# RetroBit.net
KiCad netlist of a schematic drawn in EAGLE
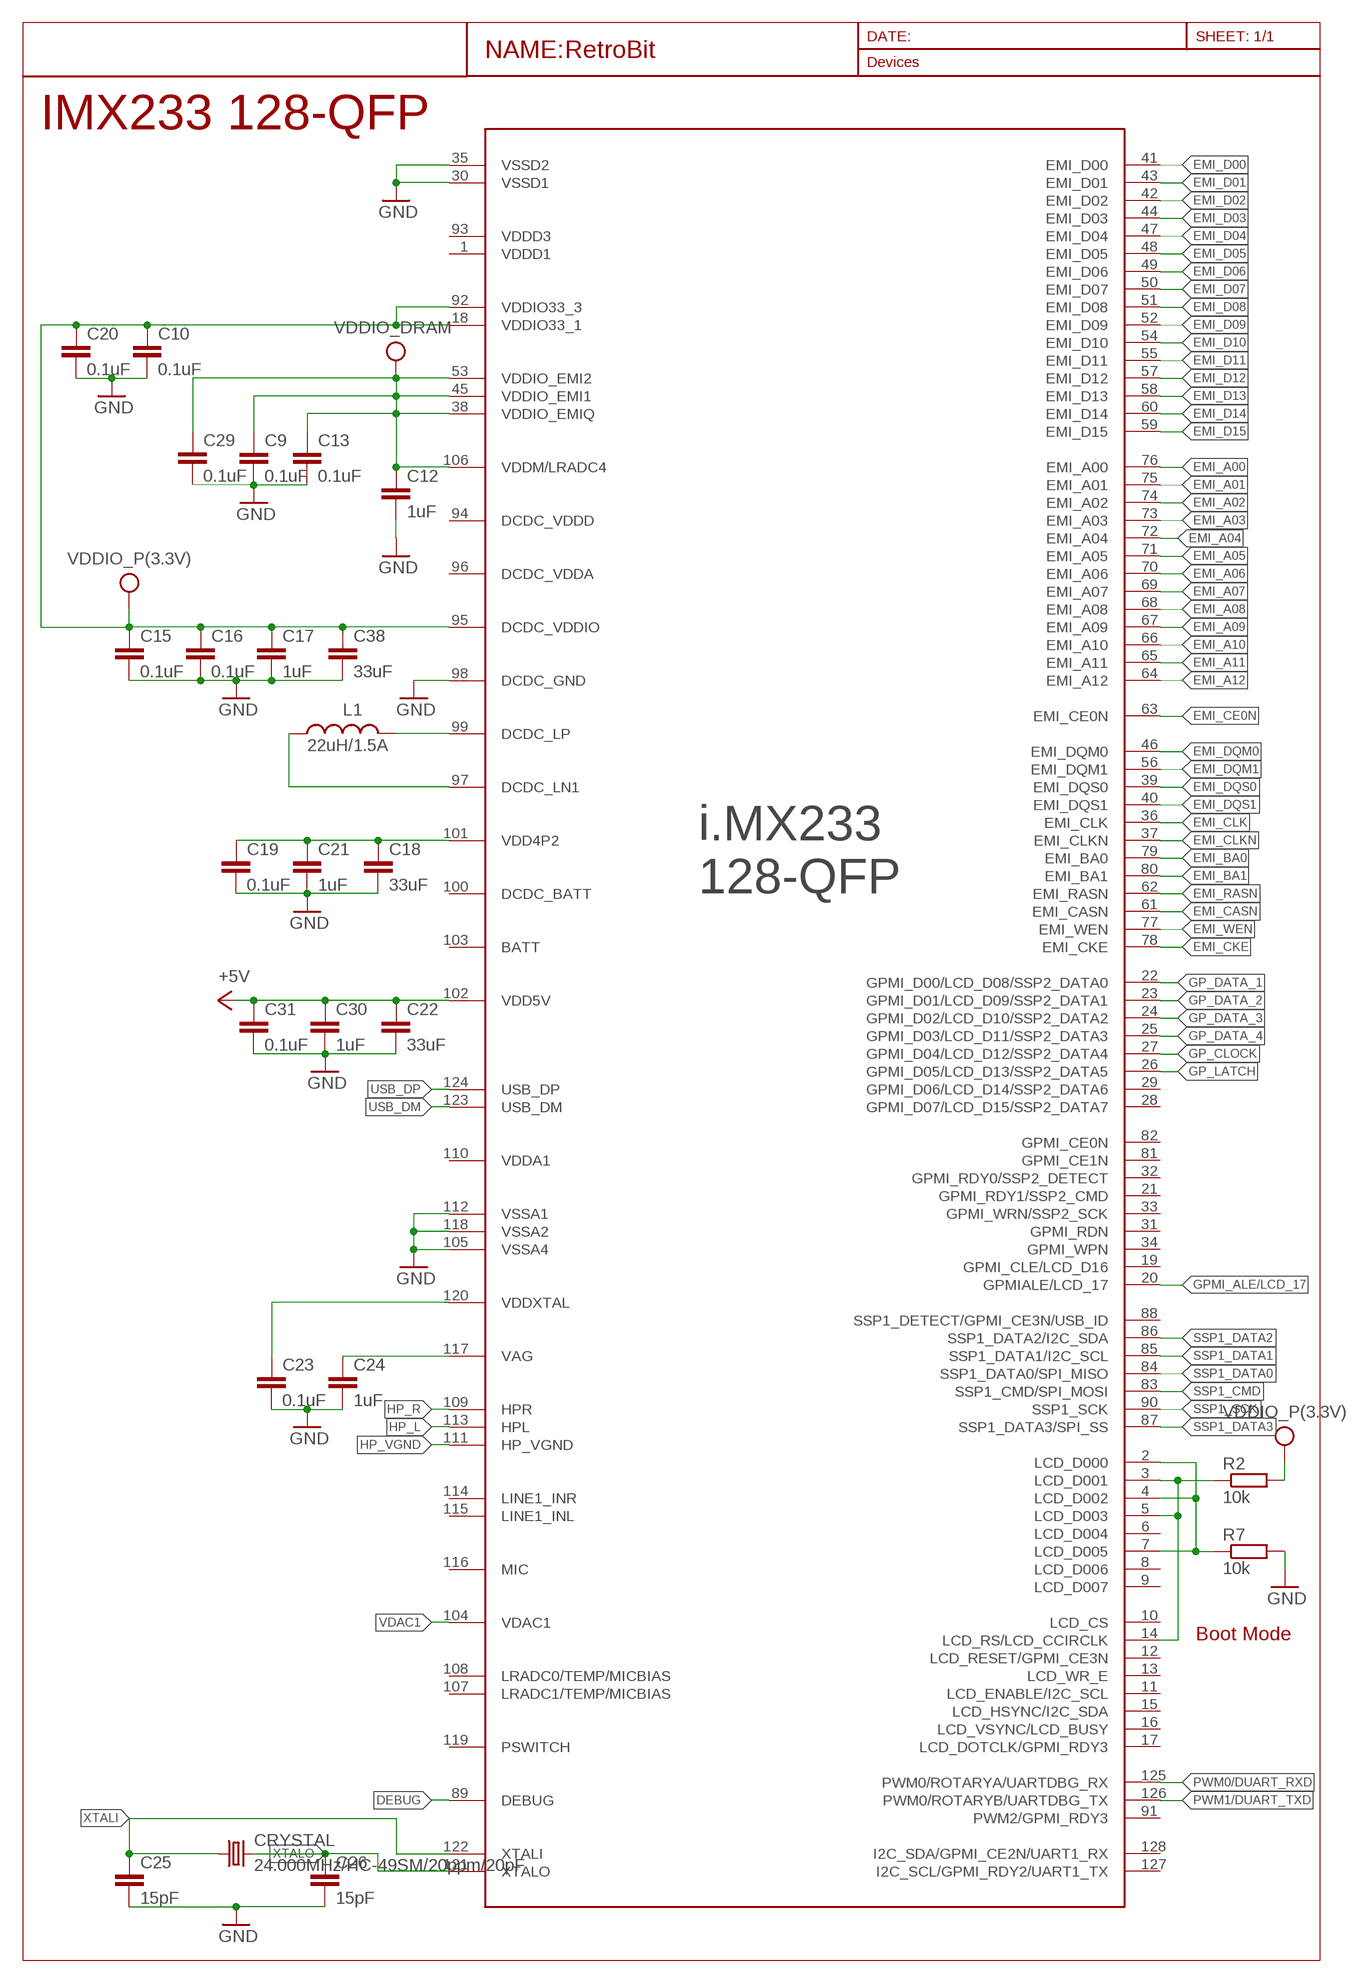
[diagram p0: schematic, sheet 1, part 1 of 2]
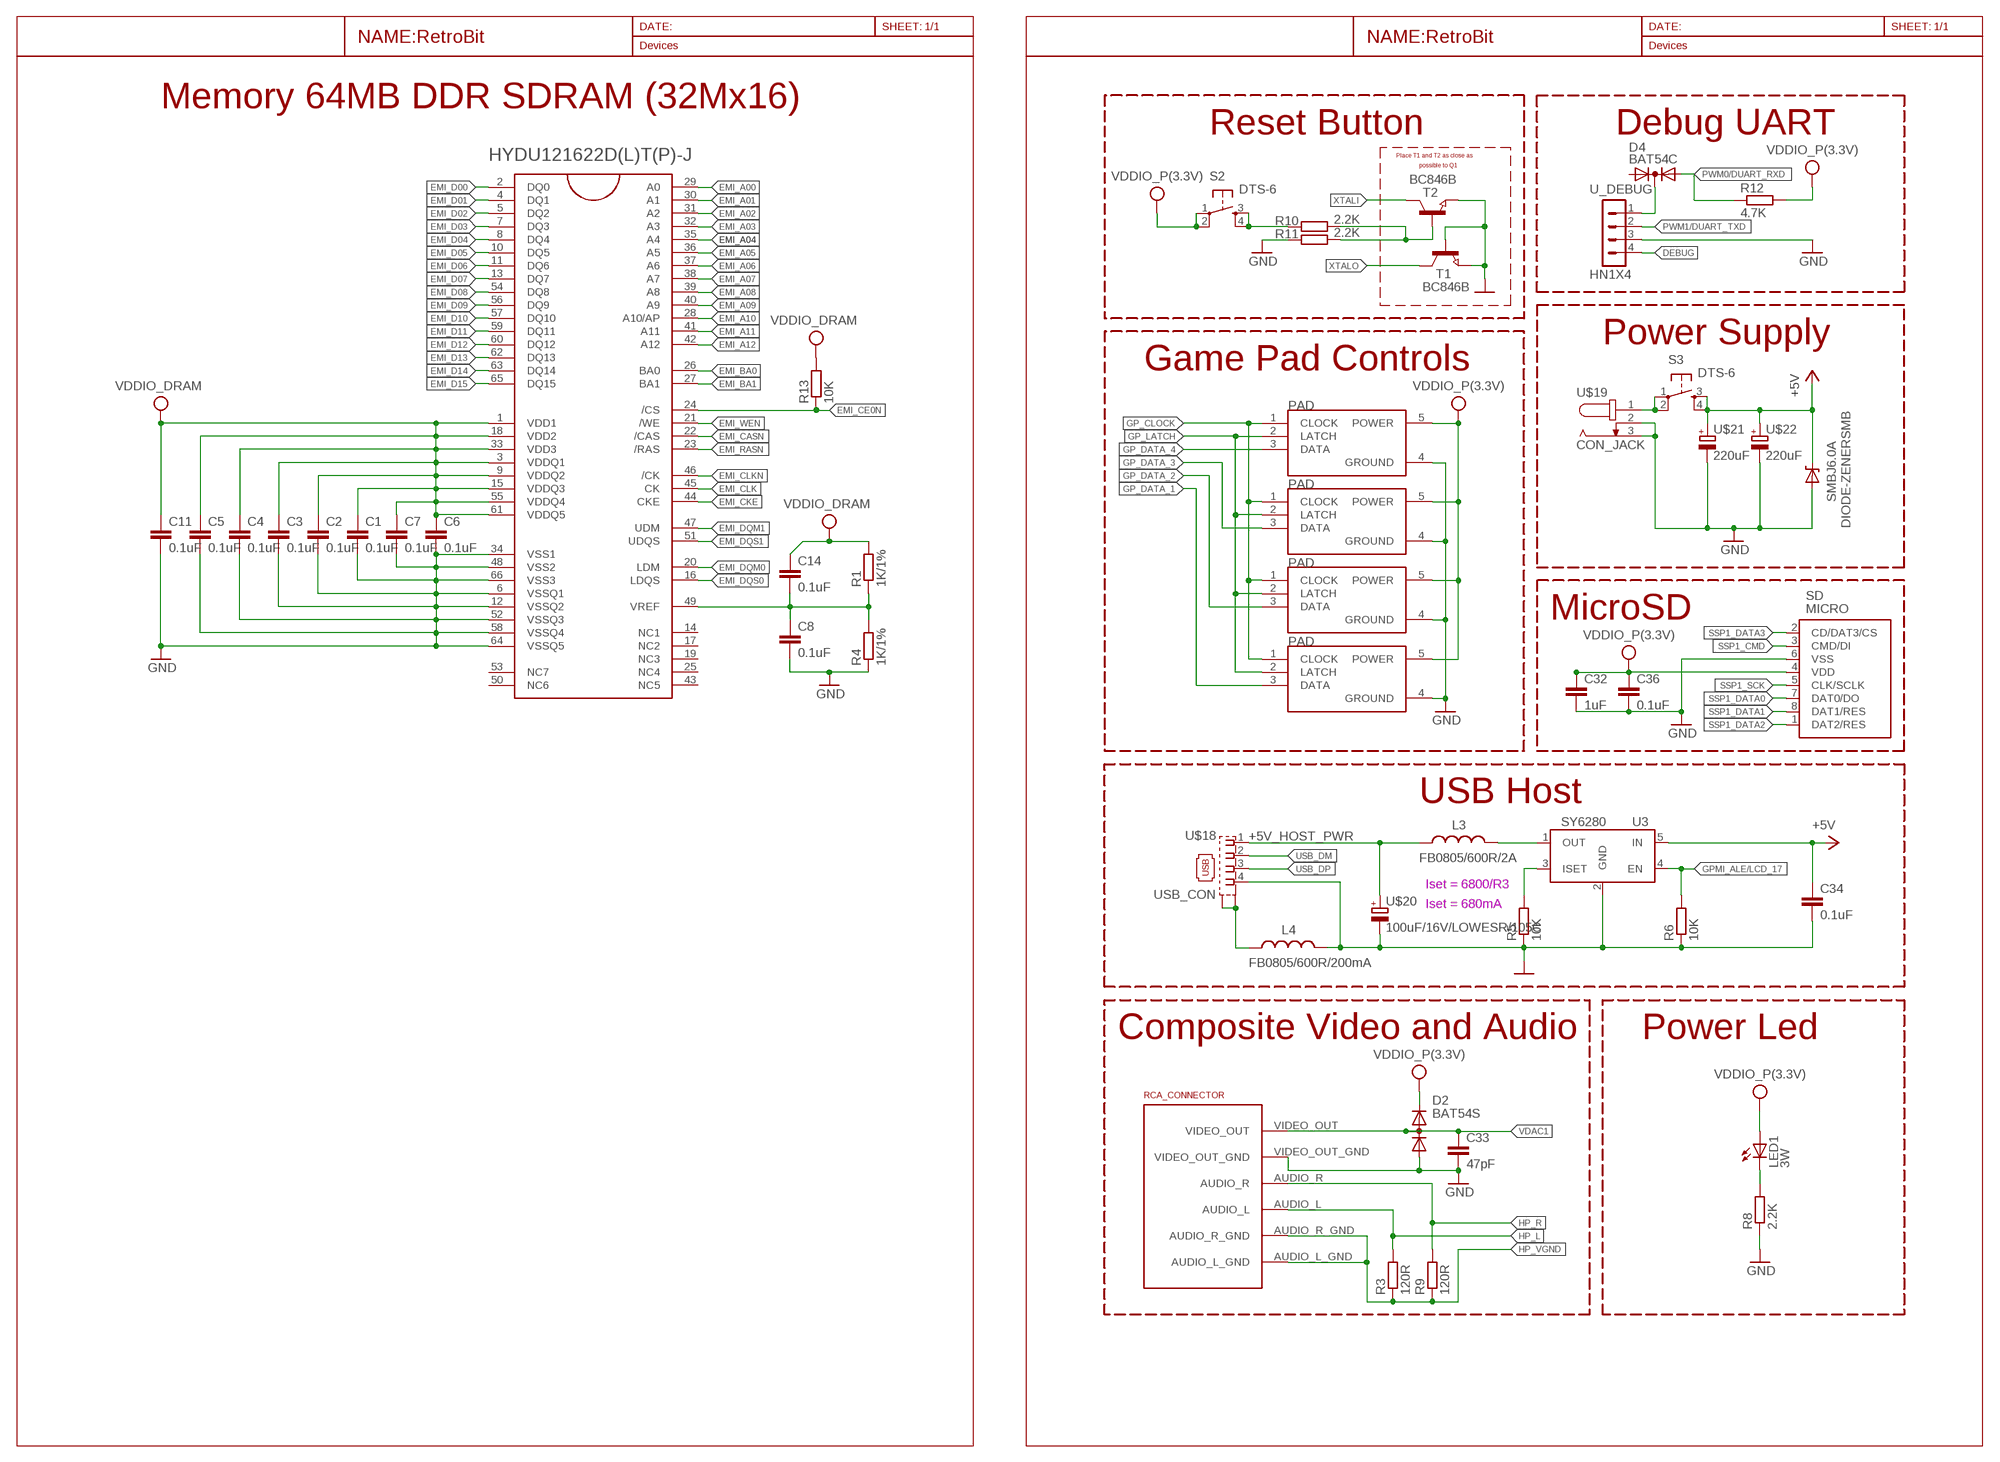
[diagram p1: schematic, sheet 1, part 2 of 2]

(export (version "E")
  (design (tool "Eeschema 10.0.6"))
  (components
    (comp (ref "C1")
      (value "0.1uF")
      (footprint "eagle-import:C0603K")
      (libsource (lib "eagle-import") (part "C-EUC0603K"))
    )
    (comp (ref "C2")
      (value "0.1uF")
      (footprint "eagle-import:C0603K")
      (libsource (lib "eagle-import") (part "C-EUC0603K"))
    )
    (comp (ref "C3")
      (value "0.1uF")
      (footprint "eagle-import:C0603K")
      (libsource (lib "eagle-import") (part "C-EUC0603K"))
    )
    (comp (ref "C4")
      (value "0.1uF")
      (footprint "eagle-import:C0603K")
      (libsource (lib "eagle-import") (part "C-EUC0603K"))
    )
    (comp (ref "C5")
      (value "0.1uF")
      (footprint "eagle-import:C0603K")
      (libsource (lib "eagle-import") (part "C-EUC0603K"))
    )
    (comp (ref "C6")
      (value "0.1uF")
      (footprint "eagle-import:C0603K")
      (libsource (lib "eagle-import") (part "C-EUC0603K"))
    )
    (comp (ref "C7")
      (value "0.1uF")
      (footprint "eagle-import:C0603K")
      (libsource (lib "eagle-import") (part "C-EUC0603K"))
    )
    (comp (ref "C8")
      (value "0.1uF")
      (footprint "eagle-import:C0603K")
      (libsource (lib "eagle-import") (part "C-EUC0603K"))
    )
    (comp (ref "C9")
      (value "0.1uF")
      (footprint "eagle-import:C0603K")
      (libsource (lib "eagle-import") (part "C-EUC0603K"))
    )
    (comp (ref "C10")
      (value "0.1uF")
      (footprint "eagle-import:C0603K")
      (libsource (lib "eagle-import") (part "C-EUC0603K"))
    )
    (comp (ref "C11")
      (value "0.1uF")
      (footprint "eagle-import:C0603K")
      (libsource (lib "eagle-import") (part "C-EUC0603K"))
    )
    (comp (ref "C12")
      (value "1uF")
      (footprint "eagle-import:C0805K")
      (libsource (lib "eagle-import") (part "C-EUC0805K"))
    )
    (comp (ref "C13")
      (value "0.1uF")
      (footprint "eagle-import:C0603K")
      (libsource (lib "eagle-import") (part "C-EUC0603K"))
    )
    (comp (ref "C14")
      (value "0.1uF")
      (footprint "eagle-import:C0603K")
      (libsource (lib "eagle-import") (part "C-EUC0603K"))
    )
    (comp (ref "C15")
      (value "0.1uF")
      (footprint "eagle-import:C0603K")
      (libsource (lib "eagle-import") (part "C-EUC0603K"))
    )
    (comp (ref "C16")
      (value "0.1uF")
      (footprint "eagle-import:C0603K")
      (libsource (lib "eagle-import") (part "C-EUC0603K"))
    )
    (comp (ref "C17")
      (value "1uF")
      (footprint "eagle-import:C0805K")
      (libsource (lib "eagle-import") (part "C-EUC0805K"))
    )
    (comp (ref "C18")
      (value "33uF")
      (footprint "eagle-import:C1210K")
      (libsource (lib "eagle-import") (part "C-EUC1210K"))
    )
    (comp (ref "C19")
      (value "0.1uF")
      (footprint "eagle-import:C0603K")
      (libsource (lib "eagle-import") (part "C-EUC0603K"))
    )
    (comp (ref "C20")
      (value "0.1uF")
      (footprint "eagle-import:C0603K")
      (libsource (lib "eagle-import") (part "C-EUC0603K"))
    )
    (comp (ref "C21")
      (value "1uF")
      (footprint "eagle-import:C0805K")
      (libsource (lib "eagle-import") (part "C-EUC0805K"))
    )
    (comp (ref "C22")
      (value "33uF")
      (footprint "eagle-import:C1210K")
      (libsource (lib "eagle-import") (part "C-EUC1210K"))
    )
    (comp (ref "C23")
      (value "0.1uF")
      (footprint "eagle-import:C0603K")
      (libsource (lib "eagle-import") (part "C-EUC0603K"))
    )
    (comp (ref "C24")
      (value "1uF")
      (footprint "eagle-import:C0805K")
      (libsource (lib "eagle-import") (part "C-EUC0805K"))
    )
    (comp (ref "C25")
      (value "15pF")
      (footprint "eagle-import:C0603K")
      (libsource (lib "eagle-import") (part "C-EUC0603K"))
    )
    (comp (ref "C26")
      (value "15pF")
      (footprint "eagle-import:C0603K")
      (libsource (lib "eagle-import") (part "C-EUC0603K"))
    )
    (comp (ref "C29")
      (value "0.1uF")
      (footprint "eagle-import:C0603K")
      (libsource (lib "eagle-import") (part "C-EUC0603K"))
    )
    (comp (ref "C30")
      (value "1uF")
      (footprint "eagle-import:C0805K")
      (libsource (lib "eagle-import") (part "C-EUC0805K"))
    )
    (comp (ref "C31")
      (value "0.1uF")
      (footprint "eagle-import:C0603K")
      (libsource (lib "eagle-import") (part "C-EUC0603K"))
    )
    (comp (ref "C32")
      (value "1uF")
      (footprint "eagle-import:C0805K")
      (libsource (lib "eagle-import") (part "C-EUC0805K"))
    )
    (comp (ref "C33")
      (value "47pF")
      (footprint "eagle-import:C0603K")
      (libsource (lib "eagle-import") (part "C-EUC0603K"))
    )
    (comp (ref "C34")
      (value "0.1uF")
      (footprint "eagle-import:C0603K")
      (libsource (lib "eagle-import") (part "C-EUC0603K"))
    )
    (comp (ref "C36")
      (value "0.1uF")
      (footprint "eagle-import:C0603K")
      (libsource (lib "eagle-import") (part "C-EUC0603K"))
    )
    (comp (ref "C38")
      (value "33uF")
      (footprint "eagle-import:C1210K")
      (libsource (lib "eagle-import") (part "C-EUC1210K"))
    )
    (comp (ref "CRYSTAL")
      (value "24.000MHz/HC-49SM/20ppm/20pF")
      (footprint "eagle-import:HC49U-V")
      (libsource (lib "eagle-import") (part "HC49U-V"))
    )
    (comp (ref "D2")
      (value "BAT54S")
      (footprint "eagle-import:SOT23C(BAT54S)")
      (libsource (lib "eagle-import") (part "DIODE_AC-AC_"))
    )
    (comp (ref "D4")
      (value "BAT54C")
      (footprint "eagle-import:SOT23C")
      (libsource (lib "eagle-import") (part "DIODE_AC-CA_"))
    )
    (comp (ref "IC1")
      (value "MCIMX233CAG4C")
      (footprint "eagle-import:MCIMX233CAG4C")
      (libsource (lib "eagle-import") (part "MCIMX233CAG4C"))
    )
    (comp (ref "L1")
      (value "22uH/1.5A")
      (footprint "eagle-import:CR75")
      (libsource (lib "eagle-import") (part "INDUCTORCR75"))
    )
    (comp (ref "L3")
      (value "FB0805/600R/2A")
      (footprint "eagle-import:0805")
      (libsource (lib "eagle-import") (part "INDUCTOR0805"))
    )
    (comp (ref "L4")
      (value "FB0805/600R/200mA")
      (footprint "eagle-import:0805")
      (libsource (lib "eagle-import") (part "INDUCTOR0805"))
    )
    (comp (ref "LED1")
      (value "3W")
      (footprint "eagle-import:LED3MM")
      (libsource (lib "eagle-import") (part "LED3MM"))
    )
    (comp (ref "R1")
      (value "1K/1%")
      (footprint "eagle-import:R0603")
      (libsource (lib "eagle-import") (part "R-EU_R0603"))
    )
    (comp (ref "R2")
      (value "10k")
      (footprint "eagle-import:R0603")
      (libsource (lib "eagle-import") (part "R-EU_R0603"))
    )
    (comp (ref "R3")
      (value "120R")
      (footprint "eagle-import:R0805")
      (libsource (lib "eagle-import") (part "R-EU_R0805"))
    )
    (comp (ref "R4")
      (value "1K/1%")
      (footprint "eagle-import:R0603")
      (libsource (lib "eagle-import") (part "R-EU_R0603"))
    )
    (comp (ref "R5")
      (value "10K")
      (footprint "eagle-import:R0805")
      (libsource (lib "eagle-import") (part "R-EU_R0805"))
    )
    (comp (ref "R6")
      (value "10K")
      (footprint "eagle-import:R0805")
      (libsource (lib "eagle-import") (part "R-EU_R0805"))
    )
    (comp (ref "R7")
      (value "10k")
      (footprint "eagle-import:R0603")
      (libsource (lib "eagle-import") (part "R-EU_R0603"))
    )
    (comp (ref "R8")
      (value "2.2K")
      (footprint "eagle-import:R0805")
      (libsource (lib "eagle-import") (part "R-EU_R0805"))
    )
    (comp (ref "R9")
      (value "120R")
      (footprint "eagle-import:R0805")
      (libsource (lib "eagle-import") (part "R-EU_R0805"))
    )
    (comp (ref "R10")
      (value "2.2K")
      (footprint "eagle-import:R0805")
      (libsource (lib "eagle-import") (part "R-EU_R0805"))
    )
    (comp (ref "R11")
      (value "2.2K")
      (footprint "eagle-import:R0805")
      (libsource (lib "eagle-import") (part "R-EU_R0805"))
    )
    (comp (ref "R12")
      (value "4.7K")
      (footprint "eagle-import:R0805")
      (libsource (lib "eagle-import") (part "R-EU_R0805"))
    )
    (comp (ref "R13")
      (value "10K")
      (footprint "eagle-import:R0805")
      (libsource (lib "eagle-import") (part "R-EU_R0805"))
    )
    (comp (ref "RCA_CONNECTOR")
      (value "RCA_CONNECTOR")
      (footprint "eagle-import:RCA_CONNECTOR")
      (libsource (lib "eagle-import") (part "RCA_CONNECTOR"))
    )
    (comp (ref "S2")
      (value "DTS-6")
      (footprint "eagle-import:DTS-6")
      (libsource (lib "eagle-import") (part "DTS-6"))
    )
    (comp (ref "S3")
      (value "DTS-6")
      (footprint "eagle-import:DTS-6")
      (libsource (lib "eagle-import") (part "DTS-6"))
    )
    (comp (ref "SD")
      (value "MICRO")
      (footprint "eagle-import:TFR-MEM-CON")
      (libsource (lib "eagle-import") (part "MICRO_SD/MMC"))
    )
    (comp (ref "SMBJ6.0A")
      (value "DIODE-ZENERSMB")
      (footprint "eagle-import:SMB-DIODE")
      (libsource (lib "eagle-import") (part "DIODE-ZENERSMB"))
    )
    (comp (ref "T1")
      (value "BC846B")
      (footprint "eagle-import:SOT23")
      (libsource (lib "eagle-import") (part "NPN-TRANSISTOR_SOT23"))
    )
    (comp (ref "T2")
      (value "BC846B")
      (footprint "eagle-import:SOT23")
      (libsource (lib "eagle-import") (part "NPN-TRANSISTOR_SOT23"))
    )
    (comp (ref "U$1")
      (value "HY5DU121622D")
      (footprint "eagle-import:HYDU121622D(L)T(P)-J")
      (libsource (lib "eagle-import") (part "HY5DU121622D"))
    )
    (comp (ref "U$3")
      (value "GAME_PAD")
      (footprint "eagle-import:GAME_PAD")
      (libsource (lib "eagle-import") (part "GAME_PAD"))
    )
    (comp (ref "U$8")
      (value "GAME_PAD")
      (footprint "eagle-import:GAME_PAD")
      (libsource (lib "eagle-import") (part "GAME_PAD"))
    )
    (comp (ref "U$9")
      (value "GAME_PAD")
      (footprint "eagle-import:GAME_PAD")
      (libsource (lib "eagle-import") (part "GAME_PAD"))
    )
    (comp (ref "U$14")
      (value "GAME_PAD")
      (footprint "eagle-import:GAME_PAD")
      (libsource (lib "eagle-import") (part "GAME_PAD"))
    )
    (comp (ref "U$18")
      (value "USB_CON")
      (footprint "eagle-import:USB_CON")
      (libsource (lib "eagle-import") (part "USB_CON"))
    )
    (comp (ref "U$19")
      (value "CON_JACK")
      (footprint "eagle-import:CON_JACK")
      (libsource (lib "eagle-import") (part "CON_JACK"))
    )
    (comp (ref "U$20")
      (value "100uF/16V/LOWESR/105C")
      (footprint "eagle-import:CPOL-EVE-2.5,6-3")
      (libsource (lib "eagle-import") (part "CPOL-EVE2.5-6.3"))
    )
    (comp (ref "U$21")
      (value "220uF")
      (footprint "eagle-import:CPOL-EVE-2.5,6-3")
      (libsource (lib "eagle-import") (part "CPOL-EVE2.5-6.3"))
    )
    (comp (ref "U$22")
      (value "220uF")
      (footprint "eagle-import:CPOL-EVE-2.5,6-3")
      (libsource (lib "eagle-import") (part "CPOL-EVE2.5-6.3"))
    )
    (comp (ref "U3")
      (value "SY6280")
      (footprint "eagle-import:SOT23-5")
      (libsource (lib "eagle-import") (part "SY6280"))
    )
    (comp (ref "U_DEBUG")
      (value "HN1X4")
      (footprint "eagle-import:HN1X4")
      (libsource (lib "eagle-import") (part "CON4HN1X4"))
    )
  )
  (nets
    (net (code "1") (name "+5V") (class "Default")
      (node (ref "C22") (pin "1") (pinfunction "1_1") (pintype "passive"))
      (node (ref "C30") (pin "1") (pinfunction "1_1") (pintype "passive"))
      (node (ref "C31") (pin "1") (pinfunction "1_1") (pintype "passive"))
      (node (ref "C34") (pin "1") (pinfunction "1_1") (pintype "passive"))
      (node (ref "IC1") (pin "102") (pinfunction "VDD5V_102") (pintype "power_in"))
      (node (ref "S3") (pin "3") (pinfunction "3_3") (pintype "passive"))
      (node (ref "S3") (pin "4") (pinfunction "4_4") (pintype "passive"))
      (node (ref "SMBJ6.0A") (pin "C") (pinfunction "C_C") (pintype "passive"))
      (node (ref "U$21") (pin "+") (pinfunction "+_+") (pintype "passive"))
      (node (ref "U$22") (pin "+") (pinfunction "+_+") (pintype "passive"))
      (node (ref "U3") (pin "5") (pinfunction "IN_5") (pintype "power_in"))
    )
    (net (code "2") (name "/+5V_HOST_PWR") (class "Default")
      (node (ref "L3") (pin "1") (pinfunction "1_1") (pintype "passive"))
      (node (ref "U$18") (pin "1") (pinfunction "1_1") (pintype "passive"))
      (node (ref "U$20") (pin "+") (pinfunction "+_+") (pintype "passive"))
    )
    (net (code "3") (name "DEBUG") (class "Default")
      (node (ref "IC1") (pin "89") (pinfunction "DEBUG_89") (pintype "input"))
      (node (ref "U_DEBUG") (pin "4") (pinfunction "4_4") (pintype "passive"))
    )
    (net (code "4") (name "EMI_A00") (class "Default")
      (node (ref "IC1") (pin "76") (pinfunction "EMI_A00_76") (pintype "bidirectional"))
      (node (ref "U$1") (pin "29") (pinfunction "A0_29") (pintype "bidirectional"))
    )
    (net (code "5") (name "EMI_A01") (class "Default")
      (node (ref "IC1") (pin "75") (pinfunction "EMI_A01_75") (pintype "bidirectional"))
      (node (ref "U$1") (pin "30") (pinfunction "A1_30") (pintype "bidirectional"))
    )
    (net (code "6") (name "EMI_A02") (class "Default")
      (node (ref "IC1") (pin "74") (pinfunction "EMI_A02_74") (pintype "bidirectional"))
      (node (ref "U$1") (pin "31") (pinfunction "A2_31") (pintype "bidirectional"))
    )
    (net (code "7") (name "EMI_A03") (class "Default")
      (node (ref "IC1") (pin "73") (pinfunction "EMI_A03_73") (pintype "bidirectional"))
      (node (ref "U$1") (pin "32") (pinfunction "A3_32") (pintype "bidirectional"))
    )
    (net (code "8") (name "EMI_A04") (class "Default")
      (node (ref "IC1") (pin "72") (pinfunction "EMI_A04_72") (pintype "bidirectional"))
      (node (ref "U$1") (pin "35") (pinfunction "A4_35") (pintype "bidirectional"))
    )
    (net (code "9") (name "EMI_A05") (class "Default")
      (node (ref "IC1") (pin "71") (pinfunction "EMI_A05_71") (pintype "bidirectional"))
      (node (ref "U$1") (pin "36") (pinfunction "A5_36") (pintype "bidirectional"))
    )
    (net (code "10") (name "EMI_A06") (class "Default")
      (node (ref "IC1") (pin "70") (pinfunction "EMI_A06_70") (pintype "bidirectional"))
      (node (ref "U$1") (pin "37") (pinfunction "A6_37") (pintype "bidirectional"))
    )
    (net (code "11") (name "EMI_A07") (class "Default")
      (node (ref "IC1") (pin "69") (pinfunction "EMI_A07_69") (pintype "bidirectional"))
      (node (ref "U$1") (pin "38") (pinfunction "A7_38") (pintype "bidirectional"))
    )
    (net (code "12") (name "EMI_A08") (class "Default")
      (node (ref "IC1") (pin "68") (pinfunction "EMI_A08_68") (pintype "bidirectional"))
      (node (ref "U$1") (pin "39") (pinfunction "A8_39") (pintype "bidirectional"))
    )
    (net (code "13") (name "EMI_A09") (class "Default")
      (node (ref "IC1") (pin "67") (pinfunction "EMI_A09_67") (pintype "bidirectional"))
      (node (ref "U$1") (pin "40") (pinfunction "A9_40") (pintype "bidirectional"))
    )
    (net (code "14") (name "EMI_A10") (class "Default")
      (node (ref "IC1") (pin "66") (pinfunction "EMI_A10_66") (pintype "bidirectional"))
      (node (ref "U$1") (pin "28") (pinfunction "A10/AP_28") (pintype "bidirectional"))
    )
    (net (code "15") (name "EMI_A11") (class "Default")
      (node (ref "IC1") (pin "65") (pinfunction "EMI_A11_65") (pintype "bidirectional"))
      (node (ref "U$1") (pin "41") (pinfunction "A11_41") (pintype "bidirectional"))
    )
    (net (code "16") (name "EMI_A12") (class "Default")
      (node (ref "IC1") (pin "64") (pinfunction "EMI_A12_64") (pintype "bidirectional"))
      (node (ref "U$1") (pin "42") (pinfunction "A12_42") (pintype "bidirectional"))
    )
    (net (code "17") (name "EMI_BA0") (class "Default")
      (node (ref "IC1") (pin "79") (pinfunction "EMI_BA0_79") (pintype "bidirectional"))
      (node (ref "U$1") (pin "26") (pinfunction "BA0_26") (pintype "bidirectional"))
    )
    (net (code "18") (name "EMI_BA1") (class "Default")
      (node (ref "IC1") (pin "80") (pinfunction "EMI_BA1_80") (pintype "bidirectional"))
      (node (ref "U$1") (pin "27") (pinfunction "BA1_27") (pintype "bidirectional"))
    )
    (net (code "19") (name "EMI_CASN") (class "Default")
      (node (ref "IC1") (pin "61") (pinfunction "EMI_CASN_61") (pintype "bidirectional"))
      (node (ref "U$1") (pin "22") (pinfunction "/CAS_22") (pintype "bidirectional"))
    )
    (net (code "20") (name "EMI_CE0N") (class "Default")
      (node (ref "IC1") (pin "63") (pinfunction "EMI_CE0N_63") (pintype "bidirectional"))
      (node (ref "R13") (pin "1") (pinfunction "1_1") (pintype "passive"))
      (node (ref "U$1") (pin "24") (pinfunction "/CS_24") (pintype "bidirectional"))
    )
    (net (code "21") (name "EMI_CKE") (class "Default")
      (node (ref "IC1") (pin "78") (pinfunction "EMI_CKE_78") (pintype "bidirectional"))
      (node (ref "U$1") (pin "44") (pinfunction "CKE_44") (pintype "bidirectional"))
    )
    (net (code "22") (name "EMI_CLK") (class "Default")
      (node (ref "IC1") (pin "36") (pinfunction "EMI_CLK_36") (pintype "bidirectional"))
      (node (ref "U$1") (pin "45") (pinfunction "CK_45") (pintype "bidirectional"))
    )
    (net (code "23") (name "EMI_CLKN") (class "Default")
      (node (ref "IC1") (pin "37") (pinfunction "EMI_CLKN_37") (pintype "bidirectional"))
      (node (ref "U$1") (pin "46") (pinfunction "/CK_46") (pintype "bidirectional"))
    )
    (net (code "24") (name "EMI_D00") (class "Default")
      (node (ref "IC1") (pin "41") (pinfunction "EMI_D00_41") (pintype "bidirectional"))
      (node (ref "U$1") (pin "2") (pinfunction "DQ0_2") (pintype "bidirectional"))
    )
    (net (code "25") (name "EMI_D01") (class "Default")
      (node (ref "IC1") (pin "43") (pinfunction "EMI_D01_43") (pintype "bidirectional"))
      (node (ref "U$1") (pin "4") (pinfunction "DQ1_4") (pintype "bidirectional"))
    )
    (net (code "26") (name "EMI_D02") (class "Default")
      (node (ref "IC1") (pin "42") (pinfunction "EMI_D02_42") (pintype "bidirectional"))
      (node (ref "U$1") (pin "5") (pinfunction "DQ2_5") (pintype "bidirectional"))
    )
    (net (code "27") (name "EMI_D03") (class "Default")
      (node (ref "IC1") (pin "44") (pinfunction "EMI_D03_44") (pintype "bidirectional"))
      (node (ref "U$1") (pin "7") (pinfunction "DQ3_7") (pintype "bidirectional"))
    )
    (net (code "28") (name "EMI_D04") (class "Default")
      (node (ref "IC1") (pin "47") (pinfunction "EMI_D04_47") (pintype "bidirectional"))
      (node (ref "U$1") (pin "8") (pinfunction "DQ4_8") (pintype "bidirectional"))
    )
    (net (code "29") (name "EMI_D05") (class "Default")
      (node (ref "IC1") (pin "48") (pinfunction "EMI_D05_48") (pintype "bidirectional"))
      (node (ref "U$1") (pin "10") (pinfunction "DQ5_10") (pintype "bidirectional"))
    )
    (net (code "30") (name "EMI_D06") (class "Default")
      (node (ref "IC1") (pin "49") (pinfunction "EMI_D06_49") (pintype "bidirectional"))
      (node (ref "U$1") (pin "11") (pinfunction "DQ6_11") (pintype "bidirectional"))
    )
    (net (code "31") (name "EMI_D07") (class "Default")
      (node (ref "IC1") (pin "50") (pinfunction "EMI_D07_50") (pintype "bidirectional"))
      (node (ref "U$1") (pin "13") (pinfunction "DQ7_13") (pintype "bidirectional"))
    )
    (net (code "32") (name "EMI_D08") (class "Default")
      (node (ref "IC1") (pin "51") (pinfunction "EMI_D08_51") (pintype "bidirectional"))
      (node (ref "U$1") (pin "54") (pinfunction "DQ8_54") (pintype "bidirectional"))
    )
    (net (code "33") (name "EMI_D09") (class "Default")
      (node (ref "IC1") (pin "52") (pinfunction "EMI_D09_52") (pintype "bidirectional"))
      (node (ref "U$1") (pin "56") (pinfunction "DQ9_56") (pintype "bidirectional"))
    )
    (net (code "34") (name "EMI_D10") (class "Default")
      (node (ref "IC1") (pin "54") (pinfunction "EMI_D10_54") (pintype "bidirectional"))
      (node (ref "U$1") (pin "57") (pinfunction "DQ10_57") (pintype "bidirectional"))
    )
    (net (code "35") (name "EMI_D11") (class "Default")
      (node (ref "IC1") (pin "55") (pinfunction "EMI_D11_55") (pintype "bidirectional"))
      (node (ref "U$1") (pin "59") (pinfunction "DQ11_59") (pintype "bidirectional"))
    )
    (net (code "36") (name "EMI_D12") (class "Default")
      (node (ref "IC1") (pin "57") (pinfunction "EMI_D12_57") (pintype "bidirectional"))
      (node (ref "U$1") (pin "60") (pinfunction "DQ12_60") (pintype "bidirectional"))
    )
    (net (code "37") (name "EMI_D13") (class "Default")
      (node (ref "IC1") (pin "58") (pinfunction "EMI_D13_58") (pintype "bidirectional"))
      (node (ref "U$1") (pin "62") (pinfunction "DQ13_62") (pintype "bidirectional"))
    )
    (net (code "38") (name "EMI_D14") (class "Default")
      (node (ref "IC1") (pin "60") (pinfunction "EMI_D14_60") (pintype "bidirectional"))
      (node (ref "U$1") (pin "63") (pinfunction "DQ14_63") (pintype "bidirectional"))
    )
    (net (code "39") (name "EMI_D15") (class "Default")
      (node (ref "IC1") (pin "59") (pinfunction "EMI_D15_59") (pintype "bidirectional"))
      (node (ref "U$1") (pin "65") (pinfunction "DQ15_65") (pintype "bidirectional"))
    )
    (net (code "40") (name "EMI_DQM0") (class "Default")
      (node (ref "IC1") (pin "46") (pinfunction "EMI_DQM0_46") (pintype "bidirectional"))
      (node (ref "U$1") (pin "20") (pinfunction "LDM_20") (pintype "bidirectional"))
    )
    (net (code "41") (name "EMI_DQM1") (class "Default")
      (node (ref "IC1") (pin "56") (pinfunction "EMI_DQM1_56") (pintype "bidirectional"))
      (node (ref "U$1") (pin "47") (pinfunction "UDM_47") (pintype "bidirectional"))
    )
    (net (code "42") (name "EMI_DQS0") (class "Default")
      (node (ref "IC1") (pin "39") (pinfunction "EMI_DQS0_39") (pintype "bidirectional"))
      (node (ref "U$1") (pin "16") (pinfunction "LDQS_16") (pintype "bidirectional"))
    )
    (net (code "43") (name "EMI_DQS1") (class "Default")
      (node (ref "IC1") (pin "40") (pinfunction "EMI_DQS1_40") (pintype "bidirectional"))
      (node (ref "U$1") (pin "51") (pinfunction "UDQS_51") (pintype "bidirectional"))
    )
    (net (code "44") (name "EMI_RASN") (class "Default")
      (node (ref "IC1") (pin "62") (pinfunction "EMI_RASN_62") (pintype "bidirectional"))
      (node (ref "U$1") (pin "23") (pinfunction "/RAS_23") (pintype "bidirectional"))
    )
    (net (code "45") (name "EMI_WEN") (class "Default")
      (node (ref "IC1") (pin "77") (pinfunction "EMI_WEN_77") (pintype "bidirectional"))
      (node (ref "U$1") (pin "21") (pinfunction "/WE_21") (pintype "bidirectional"))
    )
    (net (code "46") (name "GND") (class "Default")
      (node (ref "C1") (pin "2") (pinfunction "2_2") (pintype "passive"))
      (node (ref "C10") (pin "2") (pinfunction "2_2") (pintype "passive"))
      (node (ref "C11") (pin "2") (pinfunction "2_2") (pintype "passive"))
      (node (ref "C12") (pin "2") (pinfunction "2_2") (pintype "passive"))
      (node (ref "C13") (pin "2") (pinfunction "2_2") (pintype "passive"))
      (node (ref "C15") (pin "2") (pinfunction "2_2") (pintype "passive"))
      (node (ref "C16") (pin "2") (pinfunction "2_2") (pintype "passive"))
      (node (ref "C17") (pin "2") (pinfunction "2_2") (pintype "passive"))
      (node (ref "C18") (pin "2") (pinfunction "2_2") (pintype "passive"))
      (node (ref "C19") (pin "2") (pinfunction "2_2") (pintype "passive"))
      (node (ref "C2") (pin "2") (pinfunction "2_2") (pintype "passive"))
      (node (ref "C20") (pin "2") (pinfunction "2_2") (pintype "passive"))
      (node (ref "C21") (pin "2") (pinfunction "2_2") (pintype "passive"))
      (node (ref "C22") (pin "2") (pinfunction "2_2") (pintype "passive"))
      (node (ref "C23") (pin "2") (pinfunction "2_2") (pintype "passive"))
      (node (ref "C24") (pin "2") (pinfunction "2_2") (pintype "passive"))
      (node (ref "C25") (pin "2") (pinfunction "2_2") (pintype "passive"))
      (node (ref "C26") (pin "2") (pinfunction "2_2") (pintype "passive"))
      (node (ref "C29") (pin "2") (pinfunction "2_2") (pintype "passive"))
      (node (ref "C3") (pin "2") (pinfunction "2_2") (pintype "passive"))
      (node (ref "C30") (pin "2") (pinfunction "2_2") (pintype "passive"))
      (node (ref "C31") (pin "2") (pinfunction "2_2") (pintype "passive"))
      (node (ref "C32") (pin "2") (pinfunction "2_2") (pintype "passive"))
      (node (ref "C33") (pin "2") (pinfunction "2_2") (pintype "passive"))
      (node (ref "C34") (pin "2") (pinfunction "2_2") (pintype "passive"))
      (node (ref "C36") (pin "2") (pinfunction "2_2") (pintype "passive"))
      (node (ref "C38") (pin "2") (pinfunction "2_2") (pintype "passive"))
      (node (ref "C4") (pin "2") (pinfunction "2_2") (pintype "passive"))
      (node (ref "C5") (pin "2") (pinfunction "2_2") (pintype "passive"))
      (node (ref "C6") (pin "2") (pinfunction "2_2") (pintype "passive"))
      (node (ref "C7") (pin "2") (pinfunction "2_2") (pintype "passive"))
      (node (ref "C8") (pin "2") (pinfunction "2_2") (pintype "passive"))
      (node (ref "C9") (pin "2") (pinfunction "2_2") (pintype "passive"))
      (node (ref "D2") (pin "1") (pinfunction "A_1") (pintype "passive"))
      (node (ref "IC1") (pin "105") (pinfunction "VSSA4_105") (pintype "bidirectional"))
      (node (ref "IC1") (pin "112") (pinfunction "VSSA1_112") (pintype "bidirectional"))
      (node (ref "IC1") (pin "118") (pinfunction "VSSA2_118") (pintype "bidirectional"))
      (node (ref "IC1") (pin "30") (pinfunction "VSSD1_30") (pintype "bidirectional"))
      (node (ref "IC1") (pin "35") (pinfunction "VSSD2_35") (pintype "bidirectional"))
      (node (ref "IC1") (pin "98") (pinfunction "DCDC_GND_98") (pintype "bidirectional"))
      (node (ref "L4") (pin "2") (pinfunction "2_2") (pintype "passive"))
      (node (ref "R11") (pin "1") (pinfunction "1_1") (pintype "passive"))
      (node (ref "R4") (pin "1") (pinfunction "1_1") (pintype "passive"))
      (node (ref "R5") (pin "1") (pinfunction "1_1") (pintype "passive"))
      (node (ref "R6") (pin "1") (pinfunction "1_1") (pintype "passive"))
      (node (ref "R7") (pin "2") (pinfunction "2_2") (pintype "passive"))
      (node (ref "R8") (pin "1") (pinfunction "1_1") (pintype "passive"))
      (node (ref "RCA_CONNECTOR") (pin "VIDEO_OUT_GND") (pinfunction "VIDEO_OUT_GND_VIDEO_OUT_GND") (pintype "input"))
      (node (ref "SD") (pin "6") (pinfunction "VSS_6") (pintype "power_in"))
      (node (ref "SMBJ6.0A") (pin "A") (pinfunction "A_A") (pintype "passive"))
      (node (ref "T1") (pin "1") (pinfunction "B_1") (pintype "passive"))
      (node (ref "T1") (pin "2") (pinfunction "E_2") (pintype "passive"))
      (node (ref "T2") (pin "2") (pinfunction "E_2") (pintype "passive"))
      (node (ref "U$1") (pin "12") (pinfunction "VSSQ2_12") (pintype "bidirectional"))
      (node (ref "U$1") (pin "34") (pinfunction "VSS1_34") (pintype "bidirectional"))
      (node (ref "U$1") (pin "48") (pinfunction "VSS2_48") (pintype "bidirectional"))
      (node (ref "U$1") (pin "52") (pinfunction "VSSQ3_52") (pintype "bidirectional"))
      (node (ref "U$1") (pin "58") (pinfunction "VSSQ4_58") (pintype "bidirectional"))
      (node (ref "U$1") (pin "6") (pinfunction "VSSQ1_6") (pintype "bidirectional"))
      (node (ref "U$1") (pin "64") (pinfunction "VSSQ5_64") (pintype "bidirectional"))
      (node (ref "U$1") (pin "66") (pinfunction "VSS3_66") (pintype "bidirectional"))
      (node (ref "U$14") (pin "4") (pinfunction "GROUND_4") (pintype "power_in"))
      (node (ref "U$18") (pin "4") (pinfunction "4_4") (pintype "passive"))
      (node (ref "U$19") (pin "2") (pinfunction "2_2") (pintype "passive"))
      (node (ref "U$19") (pin "3") (pinfunction "1_3") (pintype "passive"))
      (node (ref "U$20") (pin "-") (pinfunction "-_-") (pintype "passive"))
      (node (ref "U$21") (pin "-") (pinfunction "-_-") (pintype "passive"))
      (node (ref "U$22") (pin "-") (pinfunction "-_-") (pintype "passive"))
      (node (ref "U$3") (pin "4") (pinfunction "GROUND_4") (pintype "power_in"))
      (node (ref "U$8") (pin "4") (pinfunction "GROUND_4") (pintype "power_in"))
      (node (ref "U$9") (pin "4") (pinfunction "GROUND_4") (pintype "power_in"))
      (node (ref "U3") (pin "2") (pinfunction "GND_2") (pintype "power_in"))
      (node (ref "U_DEBUG") (pin "3") (pinfunction "3_3") (pintype "passive"))
    )
    (net (code "47") (name "GPMI_ALE{slash}LCD_17") (class "Default")
      (node (ref "IC1") (pin "20") (pinfunction "GPMIALE/LCD_17_20") (pintype "bidirectional"))
      (node (ref "R6") (pin "2") (pinfunction "2_2") (pintype "passive"))
      (node (ref "U3") (pin "4") (pinfunction "EN_4") (pintype "bidirectional"))
    )
    (net (code "48") (name "GP_CLOCK") (class "Default")
      (node (ref "IC1") (pin "27") (pinfunction "GPMI_D04/LCD_D12/SSP2_DATA4_27") (pintype "bidirectional"))
      (node (ref "U$14") (pin "1") (pinfunction "CLOCK_1") (pintype "bidirectional"))
      (node (ref "U$3") (pin "1") (pinfunction "CLOCK_1") (pintype "bidirectional"))
      (node (ref "U$8") (pin "1") (pinfunction "CLOCK_1") (pintype "bidirectional"))
      (node (ref "U$9") (pin "1") (pinfunction "CLOCK_1") (pintype "bidirectional"))
    )
    (net (code "49") (name "GP_DATA_1") (class "Default")
      (node (ref "IC1") (pin "22") (pinfunction "GPMI_D00/LCD_D08/SSP2_DATA0_22") (pintype "bidirectional"))
      (node (ref "U$14") (pin "3") (pinfunction "DATA_3") (pintype "bidirectional"))
    )
    (net (code "50") (name "GP_DATA_2") (class "Default")
      (node (ref "IC1") (pin "23") (pinfunction "GPMI_D01/LCD_D09/SSP2_DATA1_23") (pintype "bidirectional"))
      (node (ref "U$9") (pin "3") (pinfunction "DATA_3") (pintype "bidirectional"))
    )
    (net (code "51") (name "GP_DATA_3") (class "Default")
      (node (ref "IC1") (pin "24") (pinfunction "GPMI_D02/LCD_D10/SSP2_DATA2_24") (pintype "bidirectional"))
      (node (ref "U$8") (pin "3") (pinfunction "DATA_3") (pintype "bidirectional"))
    )
    (net (code "52") (name "GP_DATA_4") (class "Default")
      (node (ref "IC1") (pin "25") (pinfunction "GPMI_D03/LCD_D11/SSP2_DATA3_25") (pintype "bidirectional"))
      (node (ref "U$3") (pin "3") (pinfunction "DATA_3") (pintype "bidirectional"))
    )
    (net (code "53") (name "GP_LATCH") (class "Default")
      (node (ref "IC1") (pin "26") (pinfunction "GPMI_D05/LCD_D13/SSP2_DATA5_26") (pintype "bidirectional"))
      (node (ref "U$14") (pin "2") (pinfunction "LATCH_2") (pintype "bidirectional"))
      (node (ref "U$3") (pin "2") (pinfunction "LATCH_2") (pintype "bidirectional"))
      (node (ref "U$8") (pin "2") (pinfunction "LATCH_2") (pintype "bidirectional"))
      (node (ref "U$9") (pin "2") (pinfunction "LATCH_2") (pintype "bidirectional"))
    )
    (net (code "54") (name "HP_L") (class "Default")
      (node (ref "IC1") (pin "113") (pinfunction "HPL_113") (pintype "output"))
      (node (ref "R3") (pin "2") (pinfunction "2_2") (pintype "passive"))
      (node (ref "RCA_CONNECTOR") (pin "AUDIO_L") (pinfunction "AUDIO_L_AUDIO_L") (pintype "input"))
    )
    (net (code "55") (name "HP_R") (class "Default")
      (node (ref "IC1") (pin "109") (pinfunction "HPR_109") (pintype "output"))
      (node (ref "R9") (pin "2") (pinfunction "2_2") (pintype "passive"))
      (node (ref "RCA_CONNECTOR") (pin "AUDIO_R") (pinfunction "AUDIO_R_AUDIO_R") (pintype "input"))
    )
    (net (code "56") (name "HP_VGND") (class "Default")
      (node (ref "IC1") (pin "111") (pinfunction "HP_VGND_111") (pintype "bidirectional"))
      (node (ref "R3") (pin "1") (pinfunction "1_1") (pintype "passive"))
      (node (ref "R9") (pin "1") (pinfunction "1_1") (pintype "passive"))
      (node (ref "RCA_CONNECTOR") (pin "AUDIO_L_GND") (pinfunction "AUDIO_L_GND_AUDIO_L_GND") (pintype "input"))
      (node (ref "RCA_CONNECTOR") (pin "AUDIO_R_GND") (pinfunction "AUDIO_R_GND_AUDIO_R_GND") (pintype "input"))
    )
    (net (code "57") (name "Net-(D4-K)") (class "Default")
      (node (ref "D4") (pin "3") (pinfunction "K_3") (pintype "passive"))
      (node (ref "U_DEBUG") (pin "1") (pinfunction "1_1") (pintype "passive"))
    )
    (net (code "58") (name "Net-(IC1-DCDC_LN1)") (class "Default")
      (node (ref "IC1") (pin "97") (pinfunction "DCDC_LN1_97") (pintype "bidirectional"))
      (node (ref "L1") (pin "P$1") (pinfunction "1_P$1") (pintype "passive"))
    )
    (net (code "59") (name "Net-(IC1-DCDC_LP)") (class "Default")
      (node (ref "IC1") (pin "99") (pinfunction "DCDC_LP_99") (pintype "bidirectional"))
      (node (ref "L1") (pin "P$2") (pinfunction "2_P$2") (pintype "passive"))
    )
    (net (code "60") (name "Net-(IC1-LCD_D000)") (class "Default")
      (node (ref "IC1") (pin "2") (pinfunction "LCD_D000_2") (pintype "bidirectional"))
      (node (ref "IC1") (pin "4") (pinfunction "LCD_D002_4") (pintype "bidirectional"))
      (node (ref "IC1") (pin "7") (pinfunction "LCD_D005_7") (pintype "bidirectional"))
      (node (ref "R7") (pin "1") (pinfunction "1_1") (pintype "passive"))
    )
    (net (code "61") (name "Net-(IC1-LCD_D001)") (class "Default")
      (node (ref "IC1") (pin "14") (pinfunction "LCD_RS/LCD_CCIRCLK_14") (pintype "bidirectional"))
      (node (ref "IC1") (pin "3") (pinfunction "LCD_D001_3") (pintype "bidirectional"))
      (node (ref "IC1") (pin "5") (pinfunction "LCD_D003_5") (pintype "bidirectional"))
      (node (ref "R2") (pin "1") (pinfunction "1_1") (pintype "passive"))
    )
    (net (code "62") (name "Net-(IC1-VAG)") (class "Default")
      (node (ref "C24") (pin "1") (pinfunction "1_1") (pintype "passive"))
      (node (ref "IC1") (pin "117") (pinfunction "VAG_117") (pintype "bidirectional"))
    )
    (net (code "63") (name "Net-(IC1-VDD4P2)") (class "Default")
      (node (ref "C18") (pin "1") (pinfunction "1_1") (pintype "passive"))
      (node (ref "C19") (pin "1") (pinfunction "1_1") (pintype "passive"))
      (node (ref "C21") (pin "1") (pinfunction "1_1") (pintype "passive"))
      (node (ref "IC1") (pin "101") (pinfunction "VDD4P2_101") (pintype "bidirectional"))
    )
    (net (code "64") (name "Net-(IC1-VDDXTAL)") (class "Default")
      (node (ref "C23") (pin "1") (pinfunction "1_1") (pintype "passive"))
      (node (ref "IC1") (pin "120") (pinfunction "VDDXTAL_120") (pintype "bidirectional"))
    )
    (net (code "65") (name "Net-(LED1-C)") (class "Default")
      (node (ref "LED1") (pin "K") (pinfunction "C_K") (pintype "passive"))
      (node (ref "R8") (pin "2") (pinfunction "2_2") (pintype "passive"))
    )
    (net (code "66") (name "Net-(R10-Pad1)") (class "Default")
      (node (ref "R10") (pin "1") (pinfunction "1_1") (pintype "passive"))
      (node (ref "S2") (pin "3") (pinfunction "3_3") (pintype "passive"))
      (node (ref "S2") (pin "4") (pinfunction "4_4") (pintype "passive"))
    )
    (net (code "67") (name "Net-(T2-B)") (class "Default")
      (node (ref "R10") (pin "2") (pinfunction "2_2") (pintype "passive"))
      (node (ref "R11") (pin "2") (pinfunction "2_2") (pintype "passive"))
      (node (ref "T2") (pin "1") (pinfunction "B_1") (pintype "passive"))
    )
    (net (code "68") (name "Net-(U$1-VREF)") (class "Default")
      (node (ref "C14") (pin "2") (pinfunction "2_2") (pintype "passive"))
      (node (ref "C8") (pin "1") (pinfunction "1_1") (pintype "passive"))
      (node (ref "R1") (pin "1") (pinfunction "1_1") (pintype "passive"))
      (node (ref "R4") (pin "2") (pinfunction "2_2") (pintype "passive"))
      (node (ref "U$1") (pin "49") (pinfunction "VREF_49") (pintype "bidirectional"))
    )
    (net (code "69") (name "Net-(U$18-S1)") (class "Default")
      (node (ref "L4") (pin "1") (pinfunction "1_1") (pintype "passive"))
      (node (ref "U$18") (pin "M1") (pinfunction "S1_M1") (pintype "passive"))
      (node (ref "U$18") (pin "M2") (pinfunction "S2_M2") (pintype "passive"))
    )
    (net (code "70") (name "Net-(U$19-3)") (class "Default")
      (node (ref "S3") (pin "1") (pinfunction "1_1") (pintype "passive"))
      (node (ref "S3") (pin "2") (pinfunction "2_2") (pintype "passive"))
      (node (ref "U$19") (pin "1") (pinfunction "3_1") (pintype "passive"))
    )
    (net (code "71") (name "Net-(U3-ISET)") (class "Default")
      (node (ref "R5") (pin "2") (pinfunction "2_2") (pintype "passive"))
      (node (ref "U3") (pin "3") (pinfunction "ISET_3") (pintype "bidirectional"))
    )
    (net (code "72") (name "Net-(U3-OUT)") (class "Default")
      (node (ref "L3") (pin "2") (pinfunction "2_2") (pintype "passive"))
      (node (ref "U3") (pin "1") (pinfunction "OUT_1") (pintype "bidirectional"))
    )
    (net (code "73") (name "PWM0{slash}DUART_RXD") (class "Default")
      (node (ref "D4") (pin "2") (pinfunction "A2_2") (pintype "passive"))
      (node (ref "IC1") (pin "125") (pinfunction "PWM0/ROTARYA/UARTDBG_RX_125") (pintype "bidirectional"))
      (node (ref "R12") (pin "1") (pinfunction "1_1") (pintype "passive"))
    )
    (net (code "74") (name "PWM1{slash}DUART_TXD") (class "Default")
      (node (ref "IC1") (pin "126") (pinfunction "PWM0/ROTARYB/UARTDBG_TX_126") (pintype "bidirectional"))
      (node (ref "U_DEBUG") (pin "2") (pinfunction "2_2") (pintype "passive"))
    )
    (net (code "75") (name "SSP1_CMD") (class "Default")
      (node (ref "IC1") (pin "83") (pinfunction "SSP1_CMD/SPI_MOSI_83") (pintype "bidirectional"))
      (node (ref "SD") (pin "3") (pinfunction "CMD/DI_3") (pintype "input"))
    )
    (net (code "76") (name "SSP1_DATA0") (class "Default")
      (node (ref "IC1") (pin "84") (pinfunction "SSP1_DATA0/SPI_MISO_84") (pintype "bidirectional"))
      (node (ref "SD") (pin "7") (pinfunction "DAT0/DO_7") (pintype "output"))
    )
    (net (code "77") (name "SSP1_DATA1") (class "Default")
      (node (ref "IC1") (pin "85") (pinfunction "SSP1_DATA1/I2C_SCL_85") (pintype "bidirectional"))
      (node (ref "SD") (pin "8") (pinfunction "DAT1/RES_8") (pintype "bidirectional"))
    )
    (net (code "78") (name "SSP1_DATA2") (class "Default")
      (node (ref "IC1") (pin "86") (pinfunction "SSP1_DATA2/I2C_SDA_86") (pintype "bidirectional"))
      (node (ref "SD") (pin "1") (pinfunction "DAT2/RES_1") (pintype "bidirectional"))
    )
    (net (code "79") (name "SSP1_DATA3") (class "Default")
      (node (ref "IC1") (pin "87") (pinfunction "SSP1_DATA3/SPI_SS_87") (pintype "bidirectional"))
      (node (ref "SD") (pin "2") (pinfunction "CD/DAT3/CS_2") (pintype "input"))
    )
    (net (code "80") (name "SSP1_SCK") (class "Default")
      (node (ref "IC1") (pin "90") (pinfunction "SSP1_SCK_90") (pintype "bidirectional"))
      (node (ref "SD") (pin "5") (pinfunction "CLK/SCLK_5") (pintype "input"))
    )
    (net (code "81") (name "USB_DM") (class "Default")
      (node (ref "IC1") (pin "123") (pinfunction "USB_DM_123") (pintype "bidirectional"))
      (node (ref "U$18") (pin "2") (pinfunction "2_2") (pintype "passive"))
    )
    (net (code "82") (name "USB_DP") (class "Default")
      (node (ref "IC1") (pin "124") (pinfunction "USB_DP_124") (pintype "bidirectional"))
      (node (ref "U$18") (pin "3") (pinfunction "3_3") (pintype "passive"))
    )
    (net (code "83") (name "VDAC1") (class "Default")
      (node (ref "C33") (pin "1") (pinfunction "1_1") (pintype "passive"))
      (node (ref "D2") (pin "3") (pinfunction "AK_3") (pintype "passive"))
      (node (ref "IC1") (pin "104") (pinfunction "VDAC1_104") (pintype "output"))
      (node (ref "RCA_CONNECTOR") (pin "VIDEO_OUT") (pinfunction "VIDEO_OUT_VIDEO_OUT") (pintype "input"))
    )
    (net (code "84") (name "VDDIO_DRAM") (class "Default")
      (node (ref "C1") (pin "1") (pinfunction "1_1") (pintype "passive"))
      (node (ref "C11") (pin "1") (pinfunction "1_1") (pintype "passive"))
      (node (ref "C12") (pin "1") (pinfunction "1_1") (pintype "passive"))
      (node (ref "C13") (pin "1") (pinfunction "1_1") (pintype "passive"))
      (node (ref "C14") (pin "1") (pinfunction "1_1") (pintype "passive"))
      (node (ref "C2") (pin "1") (pinfunction "1_1") (pintype "passive"))
      (node (ref "C29") (pin "1") (pinfunction "1_1") (pintype "passive"))
      (node (ref "C3") (pin "1") (pinfunction "1_1") (pintype "passive"))
      (node (ref "C4") (pin "1") (pinfunction "1_1") (pintype "passive"))
      (node (ref "C5") (pin "1") (pinfunction "1_1") (pintype "passive"))
      (node (ref "C6") (pin "1") (pinfunction "1_1") (pintype "passive"))
      (node (ref "C7") (pin "1") (pinfunction "1_1") (pintype "passive"))
      (node (ref "C9") (pin "1") (pinfunction "1_1") (pintype "passive"))
      (node (ref "IC1") (pin "106") (pinfunction "VDDM/LRADC4_106") (pintype "bidirectional"))
      (node (ref "IC1") (pin "38") (pinfunction "VDDIO_EMIQ_38") (pintype "bidirectional"))
      (node (ref "IC1") (pin "45") (pinfunction "VDDIO_EMI1_45") (pintype "bidirectional"))
      (node (ref "IC1") (pin "53") (pinfunction "VDDIO_EMI2_53") (pintype "bidirectional"))
      (node (ref "R1") (pin "2") (pinfunction "2_2") (pintype "passive"))
      (node (ref "R13") (pin "2") (pinfunction "2_2") (pintype "passive"))
      (node (ref "U$1") (pin "1") (pinfunction "VDD1_1") (pintype "bidirectional"))
      (node (ref "U$1") (pin "15") (pinfunction "VDDQ3_15") (pintype "bidirectional"))
      (node (ref "U$1") (pin "18") (pinfunction "VDD2_18") (pintype "bidirectional"))
      (node (ref "U$1") (pin "3") (pinfunction "VDDQ1_3") (pintype "bidirectional"))
      (node (ref "U$1") (pin "33") (pinfunction "VDD3_33") (pintype "bidirectional"))
      (node (ref "U$1") (pin "55") (pinfunction "VDDQ4_55") (pintype "bidirectional"))
      (node (ref "U$1") (pin "61") (pinfunction "VDDQ5_61") (pintype "bidirectional"))
      (node (ref "U$1") (pin "9") (pinfunction "VDDQ2_9") (pintype "bidirectional"))
    )
    (net (code "85") (name "VDDIO_P(3.3V)") (class "Default")
      (node (ref "C10") (pin "1") (pinfunction "1_1") (pintype "passive"))
      (node (ref "C15") (pin "1") (pinfunction "1_1") (pintype "passive"))
      (node (ref "C16") (pin "1") (pinfunction "1_1") (pintype "passive"))
      (node (ref "C17") (pin "1") (pinfunction "1_1") (pintype "passive"))
      (node (ref "C20") (pin "1") (pinfunction "1_1") (pintype "passive"))
      (node (ref "C32") (pin "1") (pinfunction "1_1") (pintype "passive"))
      (node (ref "C36") (pin "1") (pinfunction "1_1") (pintype "passive"))
      (node (ref "C38") (pin "1") (pinfunction "1_1") (pintype "passive"))
      (node (ref "D2") (pin "2") (pinfunction "K_2") (pintype "passive"))
      (node (ref "IC1") (pin "18") (pinfunction "VDDIO33_1_18") (pintype "bidirectional"))
      (node (ref "IC1") (pin "92") (pinfunction "VDDIO33_3_92") (pintype "bidirectional"))
      (node (ref "IC1") (pin "95") (pinfunction "DCDC_VDDIO_95") (pintype "power_in"))
      (node (ref "LED1") (pin "A") (pinfunction "A_A") (pintype "passive"))
      (node (ref "R12") (pin "2") (pinfunction "2_2") (pintype "passive"))
      (node (ref "R2") (pin "2") (pinfunction "2_2") (pintype "passive"))
      (node (ref "S2") (pin "1") (pinfunction "1_1") (pintype "passive"))
      (node (ref "S2") (pin "2") (pinfunction "2_2") (pintype "passive"))
      (node (ref "SD") (pin "4") (pinfunction "VDD_4") (pintype "power_in"))
      (node (ref "U$14") (pin "5") (pinfunction "POWER_5") (pintype "power_in"))
      (node (ref "U$3") (pin "5") (pinfunction "POWER_5") (pintype "power_in"))
      (node (ref "U$8") (pin "5") (pinfunction "POWER_5") (pintype "power_in"))
      (node (ref "U$9") (pin "5") (pinfunction "POWER_5") (pintype "power_in"))
    )
    (net (code "86") (name "XTALI") (class "Default")
      (node (ref "C25") (pin "1") (pinfunction "1_1") (pintype "passive"))
      (node (ref "CRYSTAL") (pin "1") (pinfunction "1_1") (pintype "passive"))
      (node (ref "IC1") (pin "122") (pinfunction "XTALI_122") (pintype "bidirectional"))
      (node (ref "T2") (pin "3") (pinfunction "C_3") (pintype "passive"))
    )
    (net (code "87") (name "XTALO") (class "Default")
      (node (ref "C26") (pin "1") (pinfunction "1_1") (pintype "passive"))
      (node (ref "CRYSTAL") (pin "2") (pinfunction "2_2") (pintype "passive"))
      (node (ref "IC1") (pin "121") (pinfunction "XTALO_121") (pintype "bidirectional"))
      (node (ref "T1") (pin "3") (pinfunction "C_3") (pintype "passive"))
    )
    (net (code "88") (name "unconnected-(D4-A1-Pad1)") (class "Default")
      (node (ref "D4") (pin "1") (pinfunction "A1_1") (pintype "passive"))
    )
    (net (code "89") (name "unconnected-(IC1-BATT-Pad103)") (class "Default")
      (node (ref "IC1") (pin "103") (pinfunction "BATT_103") (pintype "bidirectional"))
    )
    (net (code "90") (name "unconnected-(IC1-DCDC_BATT-Pad100)") (class "Default")
      (node (ref "IC1") (pin "100") (pinfunction "DCDC_BATT_100") (pintype "bidirectional"))
    )
    (net (code "91") (name "unconnected-(IC1-DCDC_VDDA-Pad96)") (class "Default")
      (node (ref "IC1") (pin "96") (pinfunction "DCDC_VDDA_96") (pintype "bidirectional"))
    )
    (net (code "92") (name "unconnected-(IC1-DCDC_VDDD-Pad94)") (class "Default")
      (node (ref "IC1") (pin "94") (pinfunction "DCDC_VDDD_94") (pintype "bidirectional"))
    )
    (net (code "93") (name "unconnected-(IC1-GPMI_CE0N-Pad82)") (class "Default")
      (node (ref "IC1") (pin "82") (pinfunction "GPMI_CE0N_82") (pintype "bidirectional"))
    )
    (net (code "94") (name "unconnected-(IC1-GPMI_CE1N-Pad81)") (class "Default")
      (node (ref "IC1") (pin "81") (pinfunction "GPMI_CE1N_81") (pintype "bidirectional"))
    )
    (net (code "95") (name "unconnected-(IC1-GPMI_CLE{slash}LCD_D16-Pad19)") (class "Default")
      (node (ref "IC1") (pin "19") (pinfunction "GPMI_CLE/LCD_D16_19") (pintype "bidirectional"))
    )
    (net (code "96") (name "unconnected-(IC1-GPMI_D06{slash}LCD_D14{slash}SSP2_DATA6-Pad29)") (class "Default")
      (node (ref "IC1") (pin "29") (pinfunction "GPMI_D06/LCD_D14/SSP2_DATA6_29") (pintype "bidirectional"))
    )
    (net (code "97") (name "unconnected-(IC1-GPMI_D07{slash}LCD_D15{slash}SSP2_DATA7-Pad28)") (class "Default")
      (node (ref "IC1") (pin "28") (pinfunction "GPMI_D07/LCD_D15/SSP2_DATA7_28") (pintype "bidirectional"))
    )
    (net (code "98") (name "unconnected-(IC1-GPMI_RDN-Pad31)") (class "Default")
      (node (ref "IC1") (pin "31") (pinfunction "GPMI_RDN_31") (pintype "bidirectional"))
    )
    (net (code "99") (name "unconnected-(IC1-GPMI_RDY0{slash}SSP2_DETECT-Pad32)") (class "Default")
      (node (ref "IC1") (pin "32") (pinfunction "GPMI_RDY0/SSP2_DETECT_32") (pintype "bidirectional"))
    )
    (net (code "100") (name "unconnected-(IC1-GPMI_RDY1{slash}SSP2_CMD-Pad21)") (class "Default")
      (node (ref "IC1") (pin "21") (pinfunction "GPMI_RDY1/SSP2_CMD_21") (pintype "bidirectional"))
    )
    (net (code "101") (name "unconnected-(IC1-GPMI_WPN-Pad34)") (class "Default")
      (node (ref "IC1") (pin "34") (pinfunction "GPMI_WPN_34") (pintype "bidirectional"))
    )
    (net (code "102") (name "unconnected-(IC1-GPMI_WRN{slash}SSP2_SCK-Pad33)") (class "Default")
      (node (ref "IC1") (pin "33") (pinfunction "GPMI_WRN/SSP2_SCK_33") (pintype "bidirectional"))
    )
    (net (code "103") (name "unconnected-(IC1-I2C_SCL{slash}GPMI_RDY2{slash}UART1_TX-Pad127)") (class "Default")
      (node (ref "IC1") (pin "127") (pinfunction "I2C_SCL/GPMI_RDY2/UART1_TX_127") (pintype "bidirectional"))
    )
    (net (code "104") (name "unconnected-(IC1-I2C_SDA{slash}GPMI_CE2N{slash}UART1_RX-Pad128)") (class "Default")
      (node (ref "IC1") (pin "128") (pinfunction "I2C_SDA/GPMI_CE2N/UART1_RX_128") (pintype "bidirectional"))
    )
    (net (code "105") (name "unconnected-(IC1-LCD_CS-Pad10)") (class "Default")
      (node (ref "IC1") (pin "10") (pinfunction "LCD_CS_10") (pintype "bidirectional"))
    )
    (net (code "106") (name "unconnected-(IC1-LCD_D004-Pad6)") (class "Default")
      (node (ref "IC1") (pin "6") (pinfunction "LCD_D004_6") (pintype "bidirectional"))
    )
    (net (code "107") (name "unconnected-(IC1-LCD_D006-Pad8)") (class "Default")
      (node (ref "IC1") (pin "8") (pinfunction "LCD_D006_8") (pintype "bidirectional"))
    )
    (net (code "108") (name "unconnected-(IC1-LCD_D007-Pad9)") (class "Default")
      (node (ref "IC1") (pin "9") (pinfunction "LCD_D007_9") (pintype "bidirectional"))
    )
    (net (code "109") (name "unconnected-(IC1-LCD_DOTCLK{slash}GPMI_RDY3-Pad17)") (class "Default")
      (node (ref "IC1") (pin "17") (pinfunction "LCD_DOTCLK/GPMI_RDY3_17") (pintype "bidirectional"))
    )
    (net (code "110") (name "unconnected-(IC1-LCD_ENABLE{slash}I2C_SCL-Pad11)") (class "Default")
      (node (ref "IC1") (pin "11") (pinfunction "LCD_ENABLE/I2C_SCL_11") (pintype "bidirectional"))
    )
    (net (code "111") (name "unconnected-(IC1-LCD_HSYNC{slash}I2C_SDA-Pad15)") (class "Default")
      (node (ref "IC1") (pin "15") (pinfunction "LCD_HSYNC/I2C_SDA_15") (pintype "bidirectional"))
    )
    (net (code "112") (name "unconnected-(IC1-LCD_RESET{slash}GPMI_CE3N-Pad12)") (class "Default")
      (node (ref "IC1") (pin "12") (pinfunction "LCD_RESET/GPMI_CE3N_12") (pintype "bidirectional"))
    )
    (net (code "113") (name "unconnected-(IC1-LCD_VSYNC{slash}LCD_BUSY-Pad16)") (class "Default")
      (node (ref "IC1") (pin "16") (pinfunction "LCD_VSYNC/LCD_BUSY_16") (pintype "bidirectional"))
    )
    (net (code "114") (name "unconnected-(IC1-LCD_WR_E-Pad13)") (class "Default")
      (node (ref "IC1") (pin "13") (pinfunction "LCD_WR_E_13") (pintype "bidirectional"))
    )
    (net (code "115") (name "unconnected-(IC1-LINE1_INL-Pad115)") (class "Default")
      (node (ref "IC1") (pin "115") (pinfunction "LINE1_INL_115") (pintype "no_connect"))
    )
    (net (code "116") (name "unconnected-(IC1-LINE1_INR-Pad114)") (class "Default")
      (node (ref "IC1") (pin "114") (pinfunction "LINE1_INR_114") (pintype "no_connect"))
    )
    (net (code "117") (name "unconnected-(IC1-LRADC0{slash}TEMP{slash}MICBIAS-Pad108)") (class "Default")
      (node (ref "IC1") (pin "108") (pinfunction "LRADC0/TEMP/MICBIAS_108") (pintype "no_connect"))
    )
    (net (code "118") (name "unconnected-(IC1-LRADC1{slash}TEMP{slash}MICBIAS-Pad107)") (class "Default")
      (node (ref "IC1") (pin "107") (pinfunction "LRADC1/TEMP/MICBIAS_107") (pintype "no_connect"))
    )
    (net (code "119") (name "unconnected-(IC1-MIC-Pad116)") (class "Default")
      (node (ref "IC1") (pin "116") (pinfunction "MIC_116") (pintype "no_connect"))
    )
    (net (code "120") (name "unconnected-(IC1-PSWITCH-Pad119)") (class "Default")
      (node (ref "IC1") (pin "119") (pinfunction "PSWITCH_119") (pintype "bidirectional"))
    )
    (net (code "121") (name "unconnected-(IC1-PWM2{slash}GPMI_RDY3-Pad91)") (class "Default")
      (node (ref "IC1") (pin "91") (pinfunction "PWM2/GPMI_RDY3_91") (pintype "bidirectional"))
    )
    (net (code "122") (name "unconnected-(IC1-SSP1_DETECT{slash}GPMI_CE3N{slash}USB_ID-Pad88)") (class "Default")
      (node (ref "IC1") (pin "88") (pinfunction "SSP1_DETECT/GPMI_CE3N/USB_ID_88") (pintype "bidirectional"))
    )
    (net (code "123") (name "unconnected-(IC1-VDDA1-Pad110)") (class "Default")
      (node (ref "IC1") (pin "110") (pinfunction "VDDA1_110") (pintype "bidirectional"))
    )
    (net (code "124") (name "unconnected-(IC1-VDDD1-Pad1)") (class "Default")
      (node (ref "IC1") (pin "1") (pinfunction "VDDD1_1") (pintype "bidirectional"))
    )
    (net (code "125") (name "unconnected-(IC1-VDDD3-Pad93)") (class "Default")
      (node (ref "IC1") (pin "93") (pinfunction "VDDD3_93") (pintype "bidirectional"))
    )
    (net (code "126") (name "unconnected-(U$1-NC1-Pad14)") (class "Default")
      (node (ref "U$1") (pin "14") (pinfunction "NC1_14") (pintype "bidirectional"))
    )
    (net (code "127") (name "unconnected-(U$1-NC2-Pad17)") (class "Default")
      (node (ref "U$1") (pin "17") (pinfunction "NC2_17") (pintype "bidirectional"))
    )
    (net (code "128") (name "unconnected-(U$1-NC3-Pad19)") (class "Default")
      (node (ref "U$1") (pin "19") (pinfunction "NC3_19") (pintype "bidirectional"))
    )
    (net (code "129") (name "unconnected-(U$1-NC4-Pad25)") (class "Default")
      (node (ref "U$1") (pin "25") (pinfunction "NC4_25") (pintype "bidirectional"))
    )
    (net (code "130") (name "unconnected-(U$1-NC5-Pad43)") (class "Default")
      (node (ref "U$1") (pin "43") (pinfunction "NC5_43") (pintype "bidirectional"))
    )
    (net (code "131") (name "unconnected-(U$1-NC6-Pad50)") (class "Default")
      (node (ref "U$1") (pin "50") (pinfunction "NC6_50") (pintype "bidirectional"))
    )
    (net (code "132") (name "unconnected-(U$1-NC7-Pad53)") (class "Default")
      (node (ref "U$1") (pin "53") (pinfunction "NC7_53") (pintype "bidirectional"))
    )
  )
)
